# gem_cape.net
KiCad netlist of a schematic drawn in EAGLE
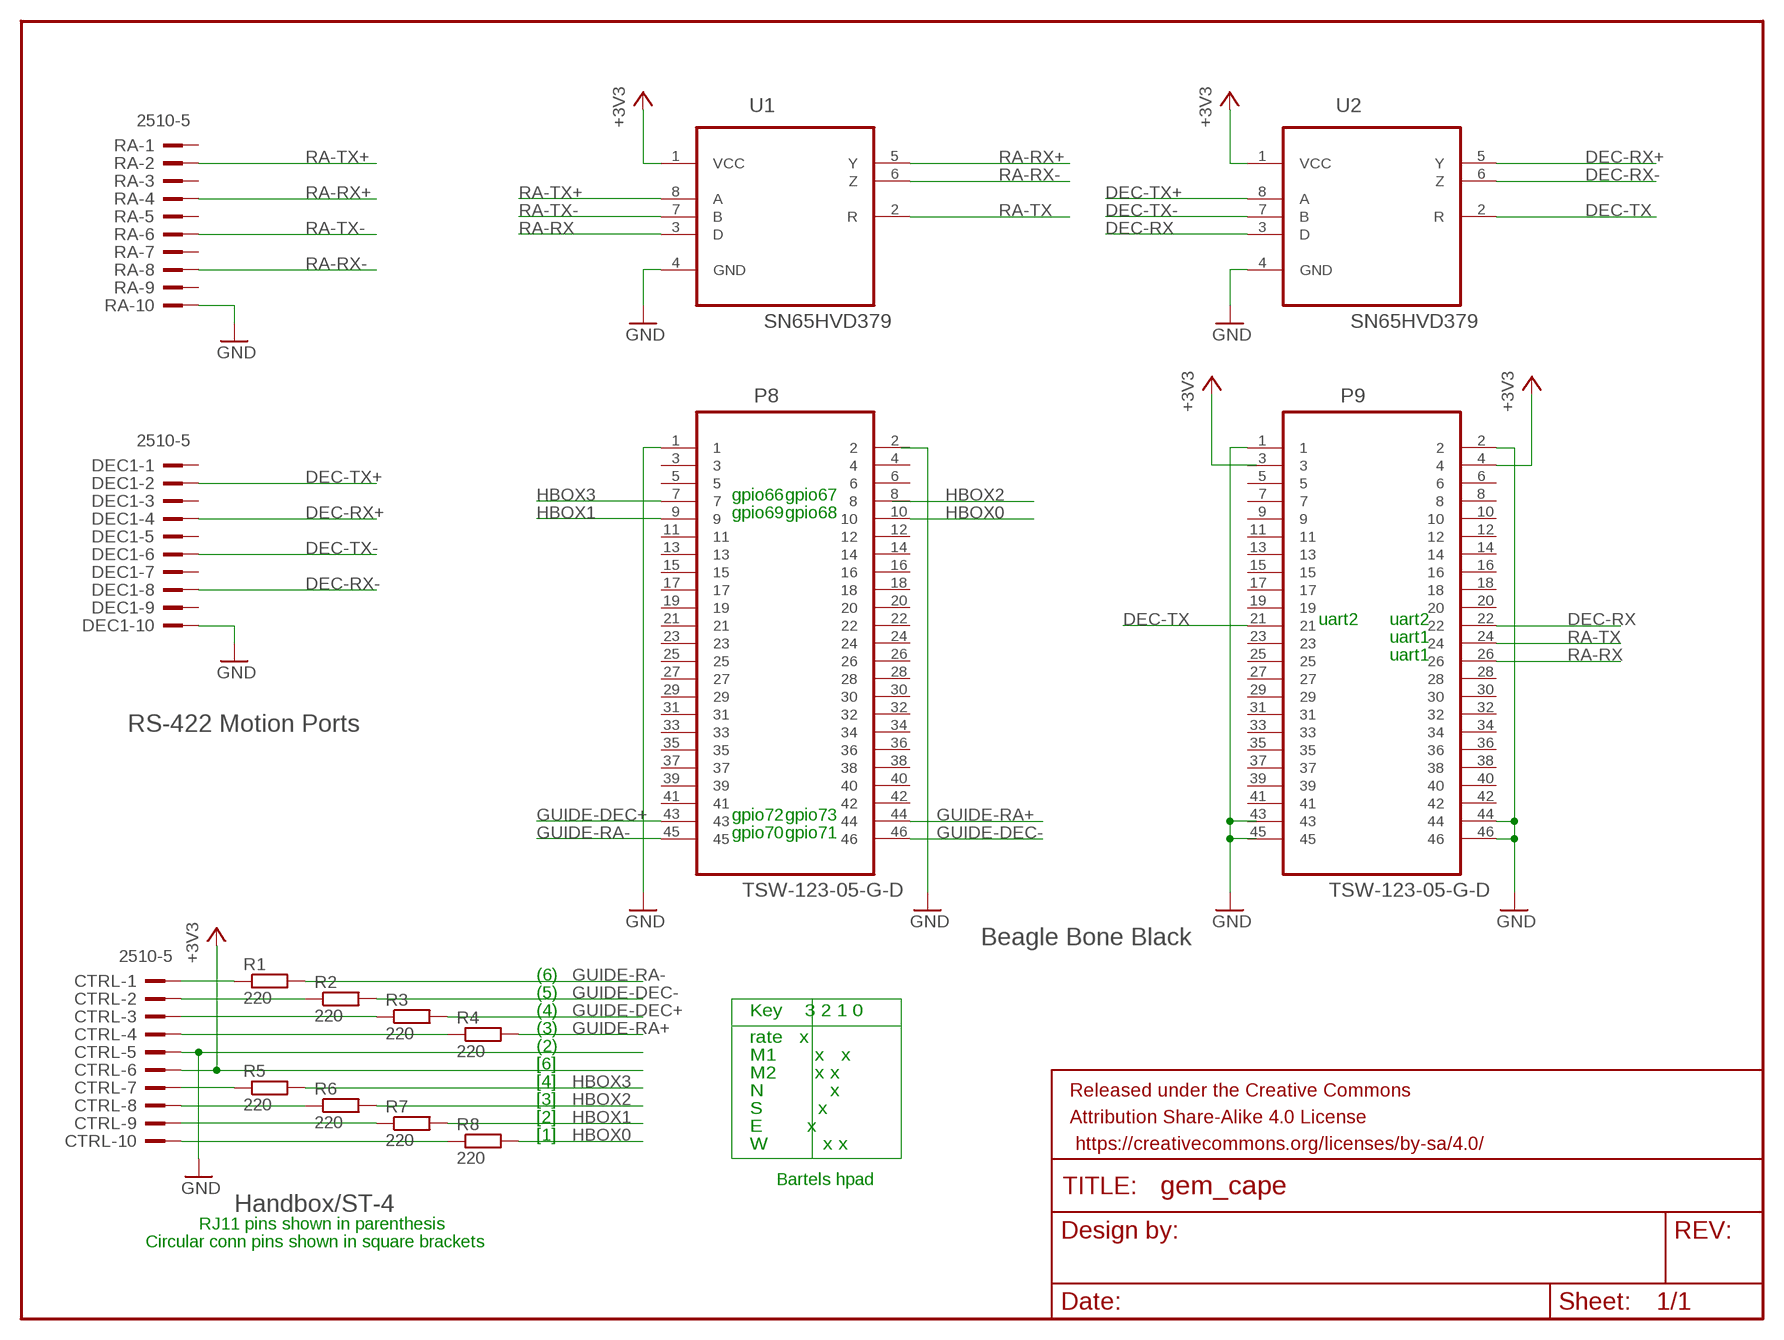
[diagram p0: schematic, sheet 1]

(export (version "E")
  (design (tool "Eeschema 10.0.6"))
  (components
    (comp (ref "CTRL")
      (value "2510-5")
      (footprint "eagle-import:PAK100_2500-5-10")
      (libsource (lib "eagle-import") (part "2510-5"))
    )
    (comp (ref "DEC1")
      (value "2510-5")
      (footprint "eagle-import:PAK100_2500-5-10")
      (libsource (lib "eagle-import") (part "2510-5"))
    )
    (comp (ref "FRAME1")
      (value "FRAME-LETTER")
      (footprint "eagle-import:CREATIVE_COMMONS")
      (libsource (lib "eagle-import") (part "FRAME-LETTER"))
    )
    (comp (ref "P8")
      (value "TSW-123-05-G-D")
      (footprint "eagle-import:SAMTEC_TSW-123-05-G-D")
      (libsource (lib "eagle-import") (part "TSW-123-05-G-D"))
    )
    (comp (ref "P9")
      (value "TSW-123-05-G-D")
      (footprint "eagle-import:SAMTEC_TSW-123-05-G-D")
      (libsource (lib "eagle-import") (part "TSW-123-05-G-D"))
    )
    (comp (ref "R1")
      (value "220")
      (footprint "eagle-import:R0805")
      (libsource (lib "eagle-import") (part "R-EU_R0805"))
    )
    (comp (ref "R2")
      (value "220")
      (footprint "eagle-import:R0805")
      (libsource (lib "eagle-import") (part "R-EU_R0805"))
    )
    (comp (ref "R3")
      (value "220")
      (footprint "eagle-import:R0805")
      (libsource (lib "eagle-import") (part "R-EU_R0805"))
    )
    (comp (ref "R4")
      (value "220")
      (footprint "eagle-import:R0805")
      (libsource (lib "eagle-import") (part "R-EU_R0805"))
    )
    (comp (ref "R5")
      (value "220")
      (footprint "eagle-import:R0805")
      (libsource (lib "eagle-import") (part "R-EU_R0805"))
    )
    (comp (ref "R6")
      (value "220")
      (footprint "eagle-import:R0805")
      (libsource (lib "eagle-import") (part "R-EU_R0805"))
    )
    (comp (ref "R7")
      (value "220")
      (footprint "eagle-import:R0805")
      (libsource (lib "eagle-import") (part "R-EU_R0805"))
    )
    (comp (ref "R8")
      (value "220")
      (footprint "eagle-import:R0805")
      (libsource (lib "eagle-import") (part "R-EU_R0805"))
    )
    (comp (ref "RA")
      (value "2510-5")
      (footprint "eagle-import:PAK100_2500-5-10")
      (libsource (lib "eagle-import") (part "2510-5"))
    )
    (comp (ref "U1")
      (value "SN65HVD379")
      (footprint "eagle-import:SOIC127P600X175-8N")
      (fields (field (name "MPN") "SN65HVD32DR") (field (name "MPN_1") "SN65HVD379"))
      (libsource (lib "eagle-import") (part "SN65HVD32DR"))
    )
    (comp (ref "U2")
      (value "SN65HVD379")
      (footprint "eagle-import:SOIC127P600X175-8N")
      (fields (field (name "MPN") "SN65HVD32DR") (field (name "MPN_1") "SN65HVD379"))
      (libsource (lib "eagle-import") (part "SN65HVD32DR"))
    )
  )
  (nets
    (net (code "1") (name "+3V3") (class "Default")
      (node (ref "CTRL") (pin "6") (pinfunction "KL_6") (pintype "passive"))
      (node (ref "P9") (pin "4") (pinfunction "4_4") (pintype "passive"))
      (node (ref "U1") (pin "1") (pinfunction "VCC_1") (pintype "power_in"))
      (node (ref "U2") (pin "1") (pinfunction "VCC_1") (pintype "power_in"))
    )
    (net (code "2") (name "/DEC-RX") (class "Default")
      (node (ref "P9") (pin "22") (pinfunction "22_22") (pintype "passive"))
      (node (ref "U2") (pin "3") (pinfunction "D_3") (pintype "input"))
    )
    (net (code "3") (name "/DEC-RX+") (class "Default")
      (node (ref "DEC1") (pin "4") (pinfunction "KL_4") (pintype "passive"))
      (node (ref "U2") (pin "5") (pinfunction "Y_5") (pintype "output"))
    )
    (net (code "4") (name "/DEC-RX-") (class "Default")
      (node (ref "DEC1") (pin "8") (pinfunction "KL_8") (pintype "passive"))
      (node (ref "U2") (pin "6") (pinfunction "Z_6") (pintype "output"))
    )
    (net (code "5") (name "/DEC-TX") (class "Default")
      (node (ref "P9") (pin "21") (pinfunction "21_21") (pintype "passive"))
      (node (ref "U2") (pin "2") (pinfunction "R_2") (pintype "output"))
    )
    (net (code "6") (name "/DEC-TX+") (class "Default")
      (node (ref "DEC1") (pin "2") (pinfunction "KL_2") (pintype "passive"))
      (node (ref "U2") (pin "8") (pinfunction "A_8") (pintype "input"))
    )
    (net (code "7") (name "/DEC-TX-") (class "Default")
      (node (ref "DEC1") (pin "6") (pinfunction "KL_6") (pintype "passive"))
      (node (ref "U2") (pin "7") (pinfunction "B_7") (pintype "input"))
    )
    (net (code "8") (name "/GUIDE-DEC+") (class "Default")
      (node (ref "P8") (pin "43") (pinfunction "43_43") (pintype "passive"))
      (node (ref "R3") (pin "2") (pinfunction "2_2") (pintype "passive"))
    )
    (net (code "9") (name "/GUIDE-DEC-") (class "Default")
      (node (ref "P8") (pin "46") (pinfunction "46_46") (pintype "passive"))
      (node (ref "R2") (pin "2") (pinfunction "2_2") (pintype "passive"))
    )
    (net (code "10") (name "/GUIDE-RA+") (class "Default")
      (node (ref "P8") (pin "44") (pinfunction "44_44") (pintype "passive"))
      (node (ref "R4") (pin "2") (pinfunction "2_2") (pintype "passive"))
    )
    (net (code "11") (name "/GUIDE-RA-") (class "Default")
      (node (ref "P8") (pin "45") (pinfunction "45_45") (pintype "passive"))
      (node (ref "R1") (pin "2") (pinfunction "2_2") (pintype "passive"))
    )
    (net (code "12") (name "/HBOX0") (class "Default")
      (node (ref "P8") (pin "10") (pinfunction "10_10") (pintype "passive"))
      (node (ref "R8") (pin "2") (pinfunction "2_2") (pintype "passive"))
    )
    (net (code "13") (name "/HBOX1") (class "Default")
      (node (ref "P8") (pin "9") (pinfunction "9_9") (pintype "passive"))
      (node (ref "R7") (pin "2") (pinfunction "2_2") (pintype "passive"))
    )
    (net (code "14") (name "/HBOX2") (class "Default")
      (node (ref "P8") (pin "8") (pinfunction "8_8") (pintype "passive"))
      (node (ref "R6") (pin "2") (pinfunction "2_2") (pintype "passive"))
    )
    (net (code "15") (name "/HBOX3") (class "Default")
      (node (ref "P8") (pin "7") (pinfunction "7_7") (pintype "passive"))
      (node (ref "R5") (pin "2") (pinfunction "2_2") (pintype "passive"))
    )
    (net (code "16") (name "/RA-RX") (class "Default")
      (node (ref "P9") (pin "26") (pinfunction "26_26") (pintype "passive"))
      (node (ref "U1") (pin "3") (pinfunction "D_3") (pintype "input"))
    )
    (net (code "17") (name "/RA-RX+") (class "Default")
      (node (ref "RA") (pin "4") (pinfunction "KL_4") (pintype "passive"))
      (node (ref "U1") (pin "5") (pinfunction "Y_5") (pintype "output"))
    )
    (net (code "18") (name "/RA-RX-") (class "Default")
      (node (ref "RA") (pin "8") (pinfunction "KL_8") (pintype "passive"))
      (node (ref "U1") (pin "6") (pinfunction "Z_6") (pintype "output"))
    )
    (net (code "19") (name "/RA-TX") (class "Default")
      (node (ref "P9") (pin "24") (pinfunction "24_24") (pintype "passive"))
      (node (ref "U1") (pin "2") (pinfunction "R_2") (pintype "output"))
    )
    (net (code "20") (name "/RA-TX+") (class "Default")
      (node (ref "RA") (pin "2") (pinfunction "KL_2") (pintype "passive"))
      (node (ref "U1") (pin "8") (pinfunction "A_8") (pintype "input"))
    )
    (net (code "21") (name "/RA-TX-") (class "Default")
      (node (ref "RA") (pin "6") (pinfunction "KL_6") (pintype "passive"))
      (node (ref "U1") (pin "7") (pinfunction "B_7") (pintype "input"))
    )
    (net (code "22") (name "GND") (class "Default")
      (node (ref "CTRL") (pin "5") (pinfunction "KL_5") (pintype "passive"))
      (node (ref "DEC1") (pin "10") (pinfunction "KL_10") (pintype "passive"))
      (node (ref "P8") (pin "1") (pinfunction "1_1") (pintype "passive"))
      (node (ref "P9") (pin "1") (pinfunction "1_1") (pintype "passive"))
      (node (ref "P9") (pin "2") (pinfunction "2_2") (pintype "passive"))
      (node (ref "P9") (pin "44") (pinfunction "44_44") (pintype "passive"))
      (node (ref "P9") (pin "46") (pinfunction "46_46") (pintype "passive"))
      (node (ref "RA") (pin "10") (pinfunction "KL_10") (pintype "passive"))
      (node (ref "U1") (pin "4") (pinfunction "GND_4") (pintype "passive"))
      (node (ref "U2") (pin "4") (pinfunction "GND_4") (pintype "passive"))
    )
    (net (code "23") (name "Net-(CTRLA-KL)") (class "Default")
      (node (ref "CTRL") (pin "1") (pinfunction "KL_1") (pintype "passive"))
      (node (ref "R1") (pin "1") (pinfunction "1_1") (pintype "passive"))
    )
    (net (code "24") (name "Net-(CTRLB-KL)") (class "Default")
      (node (ref "CTRL") (pin "10") (pinfunction "KL_10") (pintype "passive"))
      (node (ref "R8") (pin "1") (pinfunction "1_1") (pintype "passive"))
    )
    (net (code "25") (name "Net-(CTRLC-KL)") (class "Default")
      (node (ref "CTRL") (pin "2") (pinfunction "KL_2") (pintype "passive"))
      (node (ref "R2") (pin "1") (pinfunction "1_1") (pintype "passive"))
    )
    (net (code "26") (name "Net-(CTRLD-KL)") (class "Default")
      (node (ref "CTRL") (pin "3") (pinfunction "KL_3") (pintype "passive"))
      (node (ref "R3") (pin "1") (pinfunction "1_1") (pintype "passive"))
    )
    (net (code "27") (name "Net-(CTRLE-KL)") (class "Default")
      (node (ref "CTRL") (pin "4") (pinfunction "KL_4") (pintype "passive"))
      (node (ref "R4") (pin "1") (pinfunction "1_1") (pintype "passive"))
    )
    (net (code "28") (name "Net-(CTRLH-KL)") (class "Default")
      (node (ref "CTRL") (pin "7") (pinfunction "KL_7") (pintype "passive"))
      (node (ref "R5") (pin "1") (pinfunction "1_1") (pintype "passive"))
    )
    (net (code "29") (name "Net-(CTRLI-KL)") (class "Default")
      (node (ref "CTRL") (pin "8") (pinfunction "KL_8") (pintype "passive"))
      (node (ref "R6") (pin "1") (pinfunction "1_1") (pintype "passive"))
    )
    (net (code "30") (name "Net-(CTRLJ-KL)") (class "Default")
      (node (ref "CTRL") (pin "9") (pinfunction "KL_9") (pintype "passive"))
      (node (ref "R7") (pin "1") (pinfunction "1_1") (pintype "passive"))
    )
    (net (code "31") (name "unconnected-(DEC1A-KL-Pad1)") (class "Default")
      (node (ref "DEC1") (pin "1") (pinfunction "KL_1") (pintype "passive"))
    )
    (net (code "32") (name "unconnected-(DEC1D-KL-Pad3)") (class "Default")
      (node (ref "DEC1") (pin "3") (pinfunction "KL_3") (pintype "passive"))
    )
    (net (code "33") (name "unconnected-(DEC1F-KL-Pad5)") (class "Default")
      (node (ref "DEC1") (pin "5") (pinfunction "KL_5") (pintype "passive"))
    )
    (net (code "34") (name "unconnected-(DEC1H-KL-Pad7)") (class "Default")
      (node (ref "DEC1") (pin "7") (pinfunction "KL_7") (pintype "passive"))
    )
    (net (code "35") (name "unconnected-(DEC1J-KL-Pad9)") (class "Default")
      (node (ref "DEC1") (pin "9") (pinfunction "KL_9") (pintype "passive"))
    )
    (net (code "36") (name "unconnected-(P8-Pad2)") (class "Default")
      (node (ref "P8") (pin "2") (pinfunction "2_2") (pintype "passive"))
    )
    (net (code "37") (name "unconnected-(P8-Pad3)") (class "Default")
      (node (ref "P8") (pin "3") (pinfunction "3_3") (pintype "passive"))
    )
    (net (code "38") (name "unconnected-(P8-Pad4)") (class "Default")
      (node (ref "P8") (pin "4") (pinfunction "4_4") (pintype "passive"))
    )
    (net (code "39") (name "unconnected-(P8-Pad5)") (class "Default")
      (node (ref "P8") (pin "5") (pinfunction "5_5") (pintype "passive"))
    )
    (net (code "40") (name "unconnected-(P8-Pad6)") (class "Default")
      (node (ref "P8") (pin "6") (pinfunction "6_6") (pintype "passive"))
    )
    (net (code "41") (name "unconnected-(P8-Pad11)") (class "Default")
      (node (ref "P8") (pin "11") (pinfunction "11_11") (pintype "passive"))
    )
    (net (code "42") (name "unconnected-(P8-Pad12)") (class "Default")
      (node (ref "P8") (pin "12") (pinfunction "12_12") (pintype "passive"))
    )
    (net (code "43") (name "unconnected-(P8-Pad13)") (class "Default")
      (node (ref "P8") (pin "13") (pinfunction "13_13") (pintype "passive"))
    )
    (net (code "44") (name "unconnected-(P8-Pad14)") (class "Default")
      (node (ref "P8") (pin "14") (pinfunction "14_14") (pintype "passive"))
    )
    (net (code "45") (name "unconnected-(P8-Pad15)") (class "Default")
      (node (ref "P8") (pin "15") (pinfunction "15_15") (pintype "passive"))
    )
    (net (code "46") (name "unconnected-(P8-Pad16)") (class "Default")
      (node (ref "P8") (pin "16") (pinfunction "16_16") (pintype "passive"))
    )
    (net (code "47") (name "unconnected-(P8-Pad17)") (class "Default")
      (node (ref "P8") (pin "17") (pinfunction "17_17") (pintype "passive"))
    )
    (net (code "48") (name "unconnected-(P8-Pad18)") (class "Default")
      (node (ref "P8") (pin "18") (pinfunction "18_18") (pintype "passive"))
    )
    (net (code "49") (name "unconnected-(P8-Pad19)") (class "Default")
      (node (ref "P8") (pin "19") (pinfunction "19_19") (pintype "passive"))
    )
    (net (code "50") (name "unconnected-(P8-Pad20)") (class "Default")
      (node (ref "P8") (pin "20") (pinfunction "20_20") (pintype "passive"))
    )
    (net (code "51") (name "unconnected-(P8-Pad21)") (class "Default")
      (node (ref "P8") (pin "21") (pinfunction "21_21") (pintype "passive"))
    )
    (net (code "52") (name "unconnected-(P8-Pad22)") (class "Default")
      (node (ref "P8") (pin "22") (pinfunction "22_22") (pintype "passive"))
    )
    (net (code "53") (name "unconnected-(P8-Pad23)") (class "Default")
      (node (ref "P8") (pin "23") (pinfunction "23_23") (pintype "passive"))
    )
    (net (code "54") (name "unconnected-(P8-Pad24)") (class "Default")
      (node (ref "P8") (pin "24") (pinfunction "24_24") (pintype "passive"))
    )
    (net (code "55") (name "unconnected-(P8-Pad25)") (class "Default")
      (node (ref "P8") (pin "25") (pinfunction "25_25") (pintype "passive"))
    )
    (net (code "56") (name "unconnected-(P8-Pad26)") (class "Default")
      (node (ref "P8") (pin "26") (pinfunction "26_26") (pintype "passive"))
    )
    (net (code "57") (name "unconnected-(P8-Pad27)") (class "Default")
      (node (ref "P8") (pin "27") (pinfunction "27_27") (pintype "passive"))
    )
    (net (code "58") (name "unconnected-(P8-Pad28)") (class "Default")
      (node (ref "P8") (pin "28") (pinfunction "28_28") (pintype "passive"))
    )
    (net (code "59") (name "unconnected-(P8-Pad29)") (class "Default")
      (node (ref "P8") (pin "29") (pinfunction "29_29") (pintype "passive"))
    )
    (net (code "60") (name "unconnected-(P8-Pad30)") (class "Default")
      (node (ref "P8") (pin "30") (pinfunction "30_30") (pintype "passive"))
    )
    (net (code "61") (name "unconnected-(P8-Pad31)") (class "Default")
      (node (ref "P8") (pin "31") (pinfunction "31_31") (pintype "passive"))
    )
    (net (code "62") (name "unconnected-(P8-Pad32)") (class "Default")
      (node (ref "P8") (pin "32") (pinfunction "32_32") (pintype "passive"))
    )
    (net (code "63") (name "unconnected-(P8-Pad33)") (class "Default")
      (node (ref "P8") (pin "33") (pinfunction "33_33") (pintype "passive"))
    )
    (net (code "64") (name "unconnected-(P8-Pad34)") (class "Default")
      (node (ref "P8") (pin "34") (pinfunction "34_34") (pintype "passive"))
    )
    (net (code "65") (name "unconnected-(P8-Pad35)") (class "Default")
      (node (ref "P8") (pin "35") (pinfunction "35_35") (pintype "passive"))
    )
    (net (code "66") (name "unconnected-(P8-Pad36)") (class "Default")
      (node (ref "P8") (pin "36") (pinfunction "36_36") (pintype "passive"))
    )
    (net (code "67") (name "unconnected-(P8-Pad37)") (class "Default")
      (node (ref "P8") (pin "37") (pinfunction "37_37") (pintype "passive"))
    )
    (net (code "68") (name "unconnected-(P8-Pad38)") (class "Default")
      (node (ref "P8") (pin "38") (pinfunction "38_38") (pintype "passive"))
    )
    (net (code "69") (name "unconnected-(P8-Pad39)") (class "Default")
      (node (ref "P8") (pin "39") (pinfunction "39_39") (pintype "passive"))
    )
    (net (code "70") (name "unconnected-(P8-Pad40)") (class "Default")
      (node (ref "P8") (pin "40") (pinfunction "40_40") (pintype "passive"))
    )
    (net (code "71") (name "unconnected-(P8-Pad41)") (class "Default")
      (node (ref "P8") (pin "41") (pinfunction "41_41") (pintype "passive"))
    )
    (net (code "72") (name "unconnected-(P8-Pad42)") (class "Default")
      (node (ref "P8") (pin "42") (pinfunction "42_42") (pintype "passive"))
    )
    (net (code "73") (name "unconnected-(P9-Pad3)") (class "Default")
      (node (ref "P9") (pin "3") (pinfunction "3_3") (pintype "passive"))
    )
    (net (code "74") (name "unconnected-(P9-Pad5)") (class "Default")
      (node (ref "P9") (pin "5") (pinfunction "5_5") (pintype "passive"))
    )
    (net (code "75") (name "unconnected-(P9-Pad6)") (class "Default")
      (node (ref "P9") (pin "6") (pinfunction "6_6") (pintype "passive"))
    )
    (net (code "76") (name "unconnected-(P9-Pad7)") (class "Default")
      (node (ref "P9") (pin "7") (pinfunction "7_7") (pintype "passive"))
    )
    (net (code "77") (name "unconnected-(P9-Pad8)") (class "Default")
      (node (ref "P9") (pin "8") (pinfunction "8_8") (pintype "passive"))
    )
    (net (code "78") (name "unconnected-(P9-Pad9)") (class "Default")
      (node (ref "P9") (pin "9") (pinfunction "9_9") (pintype "passive"))
    )
    (net (code "79") (name "unconnected-(P9-Pad10)") (class "Default")
      (node (ref "P9") (pin "10") (pinfunction "10_10") (pintype "passive"))
    )
    (net (code "80") (name "unconnected-(P9-Pad11)") (class "Default")
      (node (ref "P9") (pin "11") (pinfunction "11_11") (pintype "passive"))
    )
    (net (code "81") (name "unconnected-(P9-Pad12)") (class "Default")
      (node (ref "P9") (pin "12") (pinfunction "12_12") (pintype "passive"))
    )
    (net (code "82") (name "unconnected-(P9-Pad13)") (class "Default")
      (node (ref "P9") (pin "13") (pinfunction "13_13") (pintype "passive"))
    )
    (net (code "83") (name "unconnected-(P9-Pad14)") (class "Default")
      (node (ref "P9") (pin "14") (pinfunction "14_14") (pintype "passive"))
    )
    (net (code "84") (name "unconnected-(P9-Pad15)") (class "Default")
      (node (ref "P9") (pin "15") (pinfunction "15_15") (pintype "passive"))
    )
    (net (code "85") (name "unconnected-(P9-Pad16)") (class "Default")
      (node (ref "P9") (pin "16") (pinfunction "16_16") (pintype "passive"))
    )
    (net (code "86") (name "unconnected-(P9-Pad17)") (class "Default")
      (node (ref "P9") (pin "17") (pinfunction "17_17") (pintype "passive"))
    )
    (net (code "87") (name "unconnected-(P9-Pad18)") (class "Default")
      (node (ref "P9") (pin "18") (pinfunction "18_18") (pintype "passive"))
    )
    (net (code "88") (name "unconnected-(P9-Pad19)") (class "Default")
      (node (ref "P9") (pin "19") (pinfunction "19_19") (pintype "passive"))
    )
    (net (code "89") (name "unconnected-(P9-Pad20)") (class "Default")
      (node (ref "P9") (pin "20") (pinfunction "20_20") (pintype "passive"))
    )
    (net (code "90") (name "unconnected-(P9-Pad23)") (class "Default")
      (node (ref "P9") (pin "23") (pinfunction "23_23") (pintype "passive"))
    )
    (net (code "91") (name "unconnected-(P9-Pad25)") (class "Default")
      (node (ref "P9") (pin "25") (pinfunction "25_25") (pintype "passive"))
    )
    (net (code "92") (name "unconnected-(P9-Pad27)") (class "Default")
      (node (ref "P9") (pin "27") (pinfunction "27_27") (pintype "passive"))
    )
    (net (code "93") (name "unconnected-(P9-Pad28)") (class "Default")
      (node (ref "P9") (pin "28") (pinfunction "28_28") (pintype "passive"))
    )
    (net (code "94") (name "unconnected-(P9-Pad29)") (class "Default")
      (node (ref "P9") (pin "29") (pinfunction "29_29") (pintype "passive"))
    )
    (net (code "95") (name "unconnected-(P9-Pad30)") (class "Default")
      (node (ref "P9") (pin "30") (pinfunction "30_30") (pintype "passive"))
    )
    (net (code "96") (name "unconnected-(P9-Pad31)") (class "Default")
      (node (ref "P9") (pin "31") (pinfunction "31_31") (pintype "passive"))
    )
    (net (code "97") (name "unconnected-(P9-Pad32)") (class "Default")
      (node (ref "P9") (pin "32") (pinfunction "32_32") (pintype "passive"))
    )
    (net (code "98") (name "unconnected-(P9-Pad33)") (class "Default")
      (node (ref "P9") (pin "33") (pinfunction "33_33") (pintype "passive"))
    )
    (net (code "99") (name "unconnected-(P9-Pad34)") (class "Default")
      (node (ref "P9") (pin "34") (pinfunction "34_34") (pintype "passive"))
    )
    (net (code "100") (name "unconnected-(P9-Pad35)") (class "Default")
      (node (ref "P9") (pin "35") (pinfunction "35_35") (pintype "passive"))
    )
    (net (code "101") (name "unconnected-(P9-Pad36)") (class "Default")
      (node (ref "P9") (pin "36") (pinfunction "36_36") (pintype "passive"))
    )
    (net (code "102") (name "unconnected-(P9-Pad37)") (class "Default")
      (node (ref "P9") (pin "37") (pinfunction "37_37") (pintype "passive"))
    )
    (net (code "103") (name "unconnected-(P9-Pad38)") (class "Default")
      (node (ref "P9") (pin "38") (pinfunction "38_38") (pintype "passive"))
    )
    (net (code "104") (name "unconnected-(P9-Pad39)") (class "Default")
      (node (ref "P9") (pin "39") (pinfunction "39_39") (pintype "passive"))
    )
    (net (code "105") (name "unconnected-(P9-Pad40)") (class "Default")
      (node (ref "P9") (pin "40") (pinfunction "40_40") (pintype "passive"))
    )
    (net (code "106") (name "unconnected-(P9-Pad41)") (class "Default")
      (node (ref "P9") (pin "41") (pinfunction "41_41") (pintype "passive"))
    )
    (net (code "107") (name "unconnected-(P9-Pad42)") (class "Default")
      (node (ref "P9") (pin "42") (pinfunction "42_42") (pintype "passive"))
    )
    (net (code "108") (name "unconnected-(P9-Pad43)") (class "Default")
      (node (ref "P9") (pin "43") (pinfunction "43_43") (pintype "passive"))
    )
    (net (code "109") (name "unconnected-(P9-Pad45)") (class "Default")
      (node (ref "P9") (pin "45") (pinfunction "45_45") (pintype "passive"))
    )
    (net (code "110") (name "unconnected-(RAA-KL-Pad1)") (class "Default")
      (node (ref "RA") (pin "1") (pinfunction "KL_1") (pintype "passive"))
    )
    (net (code "111") (name "unconnected-(RAD-KL-Pad3)") (class "Default")
      (node (ref "RA") (pin "3") (pinfunction "KL_3") (pintype "passive"))
    )
    (net (code "112") (name "unconnected-(RAF-KL-Pad5)") (class "Default")
      (node (ref "RA") (pin "5") (pinfunction "KL_5") (pintype "passive"))
    )
    (net (code "113") (name "unconnected-(RAH-KL-Pad7)") (class "Default")
      (node (ref "RA") (pin "7") (pinfunction "KL_7") (pintype "passive"))
    )
    (net (code "114") (name "unconnected-(RAJ-KL-Pad9)") (class "Default")
      (node (ref "RA") (pin "9") (pinfunction "KL_9") (pintype "passive"))
    )
  )
)
